# 0_2.net
KiCad netlist of a schematic drawn in EAGLE
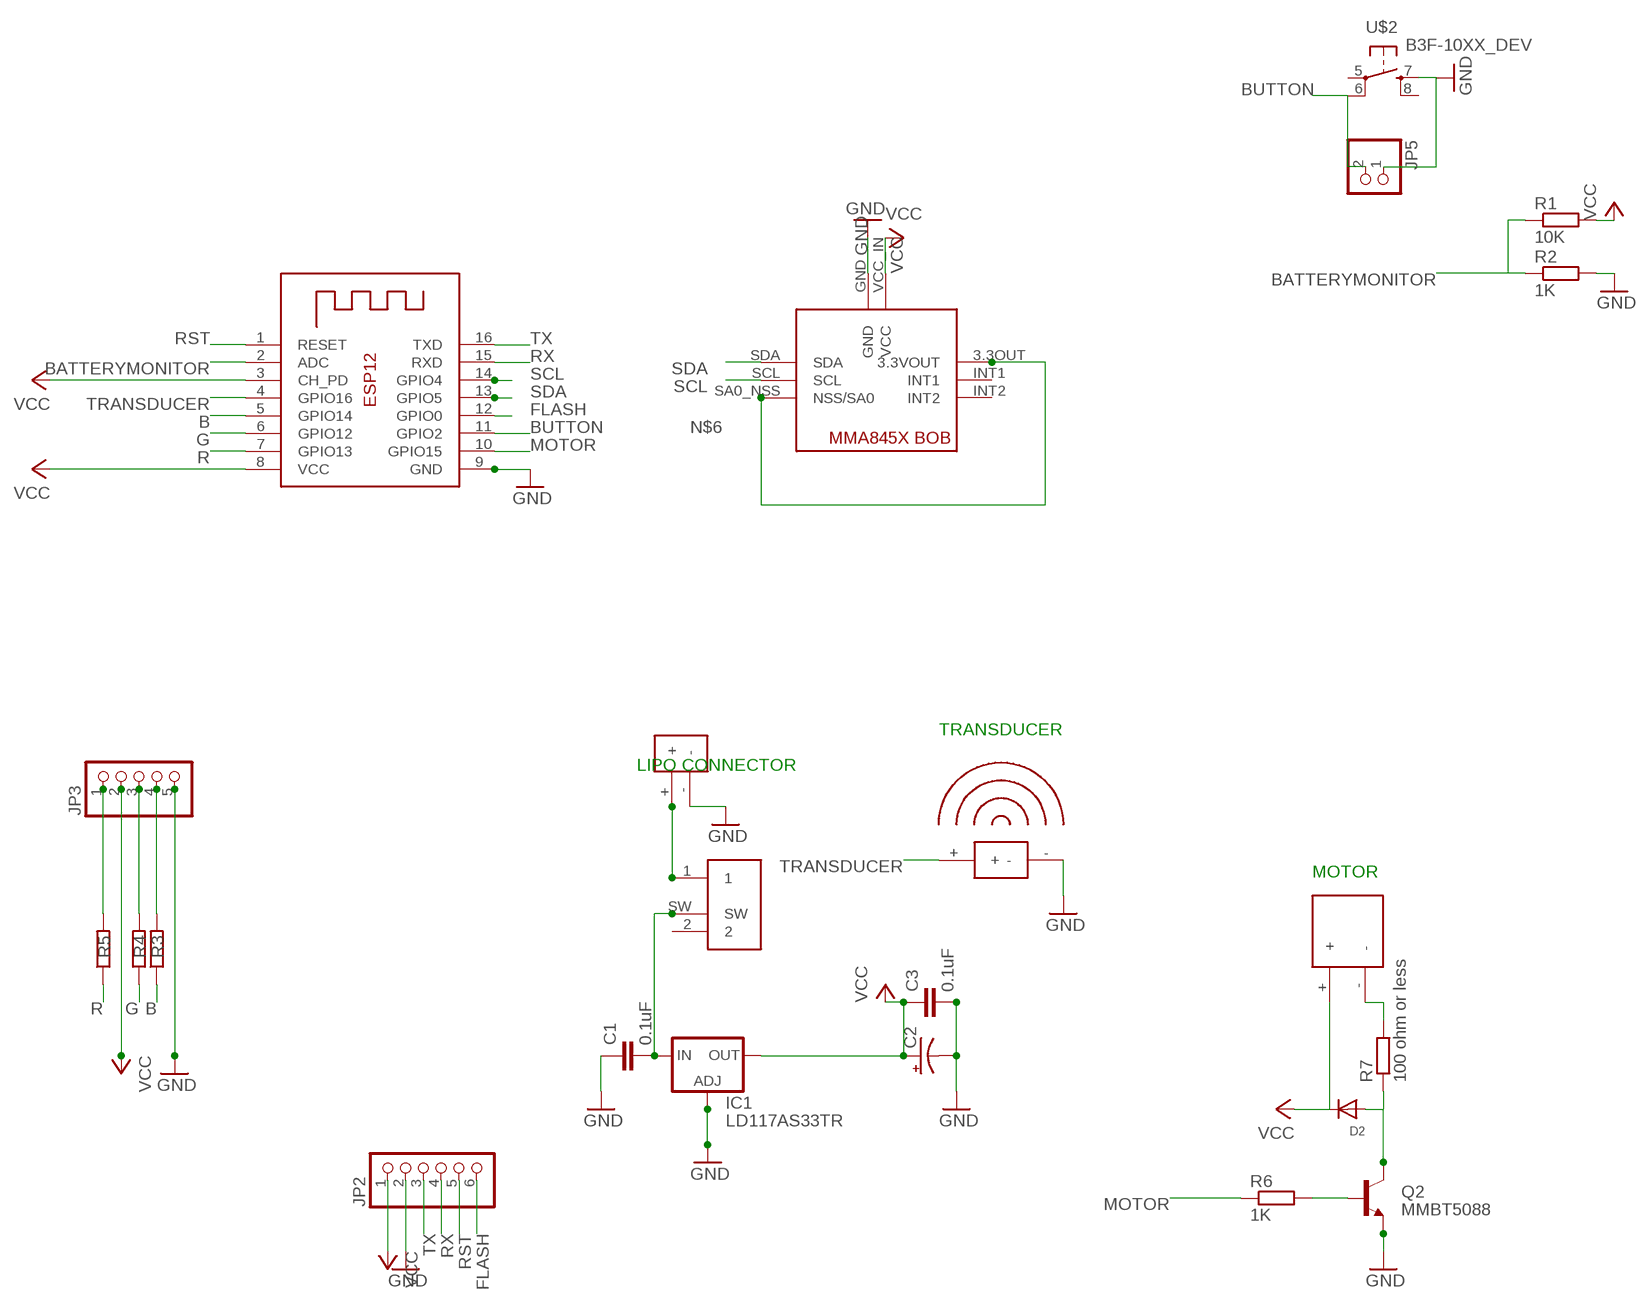
[diagram p0: schematic, sheet 1]

(export (version "E")
  (design (tool "Eeschema 10.0.6"))
  (components
    (comp (ref "C1")
      (value "0.1uF")
      (footprint "eagle-import:0805")
      (libsource (lib "eagle-import") (part "CAP0805"))
    )
    (comp (ref "C2")
      (value "100UF-25V-20%(PTH)")
      (footprint "eagle-import:CPOL-RADIAL-100UF-25V")
      (libsource (lib "eagle-import") (part "100UF-25V-20%(PTH)"))
    )
    (comp (ref "C3")
      (value "0.1uF")
      (footprint "eagle-import:0805")
      (libsource (lib "eagle-import") (part "CAP0805"))
    )
    (comp (ref "D2")
      (value "DIODE_SOD-123FL")
      (footprint "eagle-import:SOD-123FL")
      (libsource (lib "eagle-import") (part "DIODE_SOD-123FL"))
    )
    (comp (ref "IC1")
      (value "LD117AS33TR")
      (footprint "eagle-import:SOT223")
      (libsource (lib "eagle-import") (part "LD117A?S33TR"))
    )
    (comp (ref "JP2")
      (value "PINHD-1X6")
      (footprint "eagle-import:1X06")
      (libsource (lib "eagle-import") (part "PINHD-1X6"))
    )
    (comp (ref "JP3")
      (value "PINHD-1X5")
      (footprint "eagle-import:1X05")
      (libsource (lib "eagle-import") (part "PINHD-1X5"))
    )
    (comp (ref "JP5")
      (value "PINHD-1X2/90")
      (footprint "eagle-import:1X02_90")
      (libsource (lib "eagle-import") (part "PINHD-1X2/90"))
    )
    (comp (ref "Q2")
      (value "MMBT5088")
      (footprint "eagle-import:SOT23-3")
      (libsource (lib "eagle-import") (part "TRANSISTOR_NPNMMBT5088"))
    )
    (comp (ref "R1")
      (value "10K")
      (footprint "eagle-import:R0805")
      (libsource (lib "eagle-import") (part "R-EU_R0805"))
    )
    (comp (ref "R2")
      (value "1K")
      (footprint "eagle-import:R0805")
      (libsource (lib "eagle-import") (part "R-EU_R0805"))
    )
    (comp (ref "R3")
      (value "1K")
      (footprint "eagle-import:R0805")
      (libsource (lib "eagle-import") (part "R-EU_R0805"))
    )
    (comp (ref "R4")
      (value "1K")
      (footprint "eagle-import:R0805")
      (libsource (lib "eagle-import") (part "R-EU_R0805"))
    )
    (comp (ref "R5")
      (value "1K")
      (footprint "eagle-import:R0805")
      (libsource (lib "eagle-import") (part "R-EU_R0805"))
    )
    (comp (ref "R6")
      (value "1K")
      (footprint "eagle-import:R0805")
      (libsource (lib "eagle-import") (part "R-EU_R0805"))
    )
    (comp (ref "R7")
      (value "100 ohm or less")
      (footprint "eagle-import:R0805")
      (libsource (lib "eagle-import") (part "R-EU_R0805"))
    )
    (comp (ref "U$1")
      (value "MMA845X_BREAKOUT")
      (footprint "eagle-import:MMA845XBOB")
      (libsource (lib "eagle-import") (part "MMA845X_BREAKOUT"))
    )
    (comp (ref "U$2")
      (value "B3F-10XX_DEV")
      (footprint "eagle-import:B3F-10XX")
      (libsource (lib "eagle-import") (part "B3F-10XX_DEV"))
    )
    (comp (ref "U$8")
      (value "TRANSDUCER")
      (footprint "eagle-import:BMT1205XH7.5")
      (libsource (lib "eagle-import") (part "TRANSDUCER"))
    )
    (comp (ref "U$11")
      (value "MICROSWITCH")
      (footprint "eagle-import:MICR_SCHIEBESCHALTER_CHINA_PAC")
      (libsource (lib "eagle-import") (part "MICROSWITCH"))
    )
    (comp (ref "U$12")
      (value "VIBROMOTOR")
      (footprint "eagle-import:VIBRO")
      (libsource (lib "eagle-import") (part "VIBROMOTOR"))
    )
    (comp (ref "U$13")
      (value "LIPO")
      (footprint "eagle-import:LIPOCON")
      (libsource (lib "eagle-import") (part "LIPO"))
    )
    (comp (ref "X2")
      (value "ESP-12")
      (footprint "eagle-import:ESP-12")
      (libsource (lib "eagle-import") (part "ESP-12"))
    )
  )
  (nets
    (net (code "1") (name "/B") (class "Default")
      (node (ref "R3") (pin "1") (pinfunction "1_1") (pintype "passive"))
      (node (ref "X2") (pin "5") (pinfunction "GPIO14_5") (pintype "bidirectional"))
    )
    (net (code "2") (name "/BATTERYMONITOR") (class "Default")
      (node (ref "R1") (pin "1") (pinfunction "1_1") (pintype "passive"))
      (node (ref "R2") (pin "1") (pinfunction "1_1") (pintype "passive"))
      (node (ref "X2") (pin "2") (pinfunction "ADC_2") (pintype "passive"))
    )
    (net (code "3") (name "/BUTTON") (class "Default")
      (node (ref "JP5") (pin "2") (pinfunction "2_2") (pintype "passive"))
      (node (ref "U$2") (pin "6") (pinfunction "P1_6") (pintype "passive"))
      (node (ref "X2") (pin "11") (pinfunction "GPIO2_11") (pintype "bidirectional"))
    )
    (net (code "4") (name "/FLASH") (class "Default")
      (node (ref "JP2") (pin "6") (pinfunction "6_6") (pintype "passive"))
      (node (ref "X2") (pin "12") (pinfunction "GPIO0_12") (pintype "bidirectional"))
    )
    (net (code "5") (name "/G") (class "Default")
      (node (ref "R4") (pin "1") (pinfunction "1_1") (pintype "passive"))
      (node (ref "X2") (pin "6") (pinfunction "GPIO12_6") (pintype "bidirectional"))
    )
    (net (code "6") (name "/MOTOR") (class "Default")
      (node (ref "R6") (pin "1") (pinfunction "1_1") (pintype "passive"))
      (node (ref "X2") (pin "10") (pinfunction "GPIO15_10") (pintype "bidirectional"))
    )
    (net (code "7") (name "/N$6") (class "Default")
      (node (ref "U$1") (pin "3.3OUT") (pinfunction "3.3VOUT_3.3OUT") (pintype "bidirectional"))
      (node (ref "U$1") (pin "SA0_NSS") (pinfunction "NSS/SA0_SA0_NSS") (pintype "bidirectional"))
    )
    (net (code "8") (name "/R") (class "Default")
      (node (ref "R5") (pin "1") (pinfunction "1_1") (pintype "passive"))
      (node (ref "X2") (pin "7") (pinfunction "GPIO13_7") (pintype "bidirectional"))
    )
    (net (code "9") (name "/RST") (class "Default")
      (node (ref "JP2") (pin "5") (pinfunction "5_5") (pintype "passive"))
      (node (ref "X2") (pin "1") (pinfunction "RESET_1") (pintype "input"))
    )
    (net (code "10") (name "/RX") (class "Default")
      (node (ref "JP2") (pin "4") (pinfunction "4_4") (pintype "passive"))
      (node (ref "X2") (pin "15") (pinfunction "RXD_15") (pintype "input"))
    )
    (net (code "11") (name "/SCL") (class "Default")
      (node (ref "U$1") (pin "SCL") (pinfunction "SCL_SCL") (pintype "bidirectional"))
      (node (ref "X2") (pin "14") (pinfunction "GPIO4_14") (pintype "bidirectional"))
    )
    (net (code "12") (name "/SDA") (class "Default")
      (node (ref "U$1") (pin "SDA") (pinfunction "SDA_SDA") (pintype "bidirectional"))
      (node (ref "X2") (pin "13") (pinfunction "GPIO5_13") (pintype "bidirectional"))
    )
    (net (code "13") (name "/TRANSDUCER") (class "Default")
      (node (ref "U$8") (pin "+") (pinfunction "+_+") (pintype "bidirectional"))
      (node (ref "X2") (pin "4") (pinfunction "GPIO16_4") (pintype "bidirectional"))
    )
    (net (code "14") (name "/TX") (class "Default")
      (node (ref "JP2") (pin "3") (pinfunction "3_3") (pintype "passive"))
      (node (ref "X2") (pin "16") (pinfunction "TXD_16") (pintype "output"))
    )
    (net (code "15") (name "GND") (class "Default")
      (node (ref "C1") (pin "1") (pinfunction "1_1") (pintype "passive"))
      (node (ref "C2") (pin "2") (pinfunction "-_2") (pintype "passive"))
      (node (ref "C3") (pin "2") (pinfunction "2_2") (pintype "passive"))
      (node (ref "IC1") (pin "1") (pinfunction "ADJ_1") (pintype "input"))
      (node (ref "JP2") (pin "2") (pinfunction "2_2") (pintype "passive"))
      (node (ref "JP3") (pin "5") (pinfunction "5_5") (pintype "passive"))
      (node (ref "JP5") (pin "1") (pinfunction "1_1") (pintype "passive"))
      (node (ref "Q2") (pin "2") (pinfunction "E_2") (pintype "passive"))
      (node (ref "R2") (pin "2") (pinfunction "2_2") (pintype "passive"))
      (node (ref "U$1") (pin "GND") (pinfunction "GND_GND") (pintype "bidirectional"))
      (node (ref "U$13") (pin "-") (pinfunction "-_-") (pintype "bidirectional"))
      (node (ref "U$2") (pin "7") (pinfunction "S_7") (pintype "passive"))
      (node (ref "U$8") (pin "-") (pinfunction "-_-") (pintype "bidirectional"))
      (node (ref "X2") (pin "9") (pinfunction "GND_9") (pintype "power_in"))
    )
    (net (code "16") (name "Net-(IC1-IN)") (class "Default")
      (node (ref "C1") (pin "2") (pinfunction "2_2") (pintype "passive"))
      (node (ref "IC1") (pin "3") (pinfunction "IN_3") (pintype "input"))
      (node (ref "U$11") (pin "SW") (pinfunction "SW_SW") (pintype "bidirectional"))
    )
    (net (code "17") (name "Net-(JP3-Pad1)") (class "Default")
      (node (ref "JP3") (pin "1") (pinfunction "1_1") (pintype "passive"))
      (node (ref "R5") (pin "2") (pinfunction "2_2") (pintype "passive"))
    )
    (net (code "18") (name "Net-(JP3-Pad3)") (class "Default")
      (node (ref "JP3") (pin "3") (pinfunction "3_3") (pintype "passive"))
      (node (ref "R4") (pin "2") (pinfunction "2_2") (pintype "passive"))
    )
    (net (code "19") (name "Net-(JP3-Pad4)") (class "Default")
      (node (ref "JP3") (pin "4") (pinfunction "4_4") (pintype "passive"))
      (node (ref "R3") (pin "2") (pinfunction "2_2") (pintype "passive"))
    )
    (net (code "20") (name "Net-(Q2-B)") (class "Default")
      (node (ref "Q2") (pin "1") (pinfunction "B_1") (pintype "passive"))
      (node (ref "R6") (pin "2") (pinfunction "2_2") (pintype "passive"))
    )
    (net (code "21") (name "Net-(Q2-C)") (class "Default")
      (node (ref "D2") (pin "A") (pinfunction "A_A") (pintype "passive"))
      (node (ref "Q2") (pin "3") (pinfunction "C_3") (pintype "passive"))
      (node (ref "R7") (pin "1") (pinfunction "1_1") (pintype "passive"))
    )
    (net (code "22") (name "Net-(R7-Pad2)") (class "Default")
      (node (ref "R7") (pin "2") (pinfunction "2_2") (pintype "passive"))
      (node (ref "U$12") (pin "-") (pinfunction "-_-") (pintype "bidirectional"))
    )
    (net (code "23") (name "Net-(U$11-Pad1)") (class "Default")
      (node (ref "U$11") (pin "1") (pinfunction "1_1") (pintype "bidirectional"))
      (node (ref "U$13") (pin "+") (pinfunction "+_+") (pintype "bidirectional"))
    )
    (net (code "24") (name "VCC") (class "Default")
      (node (ref "C2") (pin "1") (pinfunction "+_1") (pintype "passive"))
      (node (ref "C3") (pin "1") (pinfunction "1_1") (pintype "passive"))
      (node (ref "D2") (pin "C") (pinfunction "C_C") (pintype "passive"))
      (node (ref "IC1") (pin "4") (pinfunction "OUT_4") (pintype "passive"))
      (node (ref "JP2") (pin "1") (pinfunction "1_1") (pintype "passive"))
      (node (ref "JP3") (pin "2") (pinfunction "2_2") (pintype "passive"))
      (node (ref "R1") (pin "2") (pinfunction "2_2") (pintype "passive"))
      (node (ref "U$1") (pin "VCC_IN") (pinfunction "VCC_VCC_IN") (pintype "bidirectional"))
      (node (ref "U$12") (pin "+") (pinfunction "+_+") (pintype "bidirectional"))
      (node (ref "X2") (pin "3") (pinfunction "CH_PD_3") (pintype "input"))
      (node (ref "X2") (pin "8") (pinfunction "VCC_8") (pintype "power_in"))
    )
    (net (code "25") (name "unconnected-(U$1-PadINT1)") (class "Default")
      (node (ref "U$1") (pin "INT1") (pinfunction "INT1_INT1") (pintype "bidirectional"))
    )
    (net (code "26") (name "unconnected-(U$1-PadINT2)") (class "Default")
      (node (ref "U$1") (pin "INT2") (pinfunction "INT2_INT2") (pintype "bidirectional"))
    )
    (net (code "27") (name "unconnected-(U$2-P-Pad5)") (class "Default")
      (node (ref "U$2") (pin "5") (pinfunction "P_5") (pintype "passive"))
    )
    (net (code "28") (name "unconnected-(U$2-S1-Pad8)") (class "Default")
      (node (ref "U$2") (pin "8") (pinfunction "S1_8") (pintype "passive"))
    )
    (net (code "29") (name "unconnected-(U$11-Pad2)") (class "Default")
      (node (ref "U$11") (pin "2") (pinfunction "2_2") (pintype "bidirectional"))
    )
  )
)
